# Qwiic_1Wire_to_I2C_Bridge_DS28E17_MILLAB.net
KiCad netlist of a schematic drawn in EAGLE
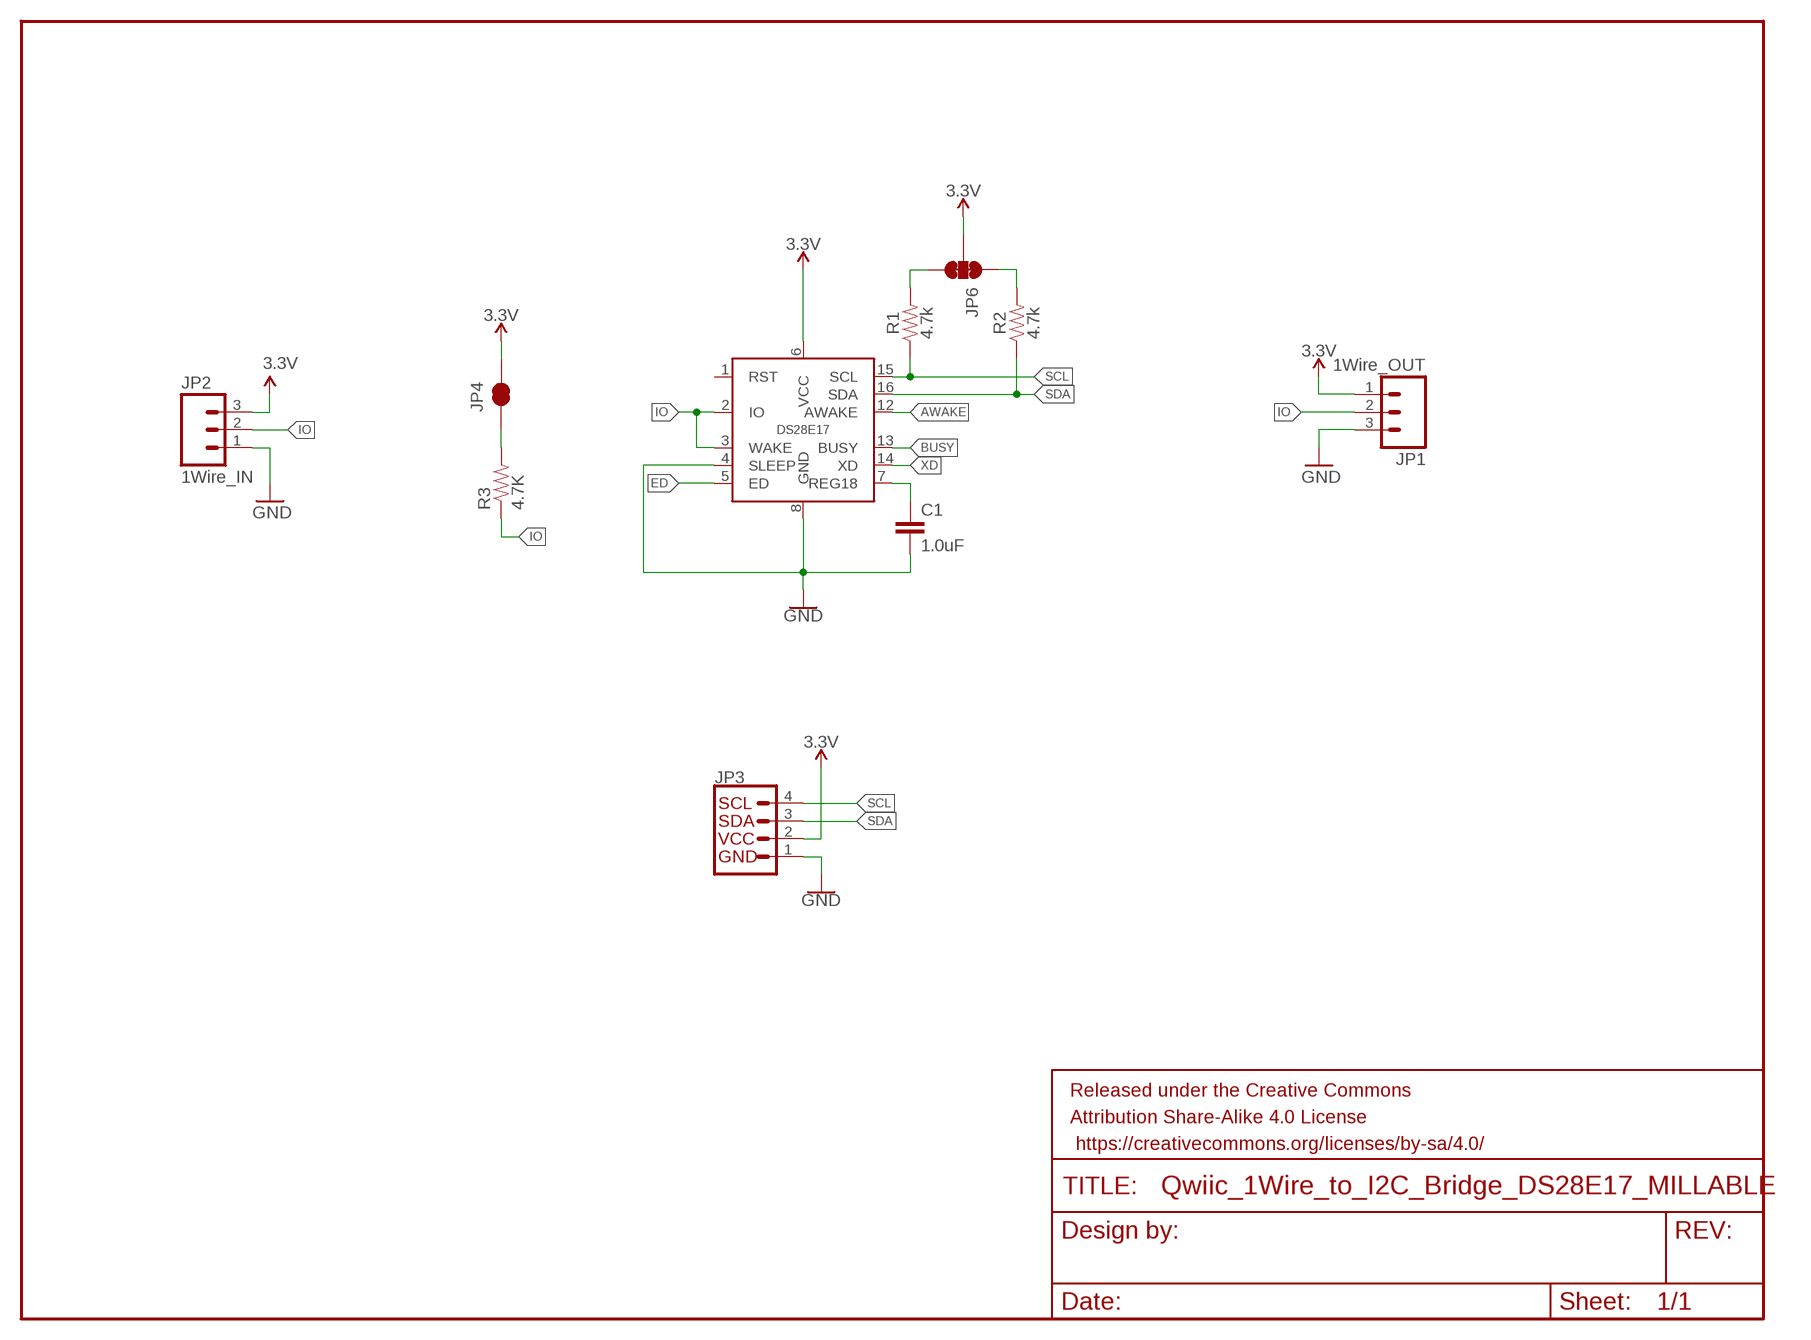
[diagram p0: schematic, sheet 1]

(export (version "E")
  (design (tool "Eeschema 10.0.6"))
  (components
    (comp (ref "C1")
      (value "1.0uF")
      (footprint "eagle-import:0603")
      (libsource (lib "eagle-import") (part "1.0UF-0603-16V-10%"))
    )
    (comp (ref "FRAME1")
      (value "FRAME-LETTER")
      (footprint "eagle-import:CREATIVE_COMMONS")
      (libsource (lib "eagle-import") (part "FRAME-LETTER"))
    )
    (comp (ref "JP1")
      (value "1Wire_OUT")
      (footprint "eagle-import:1X03")
      (libsource (lib "eagle-import") (part "M03PTH"))
    )
    (comp (ref "JP2")
      (value "1Wire_IN")
      (footprint "eagle-import:1X03")
      (libsource (lib "eagle-import") (part "M03PTH"))
    )
    (comp (ref "JP3")
      (value "I2C_STANDARDJS-1MM")
      (footprint "eagle-import:1X04_1MM_RA")
      (libsource (lib "eagle-import") (part "I2C_STANDARDJS-1MM"))
    )
    (comp (ref "JP4")
      (value "JUMPER-SMT_2_NC_TRACE_NO-SILK")
      (footprint "eagle-import:SMT-JUMPER_2_NC_TRACE_NO-SILK")
      (libsource (lib "eagle-import") (part "JUMPER-SMT_2_NC_TRACE_NO-SILK"))
    )
    (comp (ref "JP6")
      (value "JUMPER-SMT_3_2-NC_TRACE_NO-SILK")
      (footprint "eagle-import:SMT-JUMPER_3_2-NC_TRACE_NO-SILK")
      (libsource (lib "eagle-import") (part "JUMPER-SMT_3_2-NC_TRACE_NO-SILK"))
    )
    (comp (ref "R1")
      (value "4.7k")
      (footprint "eagle-import:0603")
      (libsource (lib "eagle-import") (part "4.7KOHM-0603-1/10W-1%"))
    )
    (comp (ref "R2")
      (value "4.7k")
      (footprint "eagle-import:0603")
      (libsource (lib "eagle-import") (part "4.7KOHM-0603-1/10W-1%"))
    )
    (comp (ref "R3")
      (value "4.7K")
      (footprint "eagle-import:0603-RES")
      (libsource (lib "eagle-import") (part "4.7KOHM-1/10W-1%(0603)"))
    )
    (comp (ref "U$2")
      (value "DS28E17")
      (footprint "eagle-import:TQFN-16_4X4")
      (libsource (lib "eagle-import") (part "DS28E17"))
    )
  )
  (nets
    (net (code "1") (name "3.3V") (class "Default")
      (node (ref "JP1") (pin "1") (pinfunction "1_1") (pintype "passive"))
      (node (ref "JP2") (pin "3") (pinfunction "3_3") (pintype "passive"))
      (node (ref "JP3") (pin "2") (pinfunction "VCC_2") (pintype "power_in"))
      (node (ref "JP4") (pin "2") (pinfunction "2_2") (pintype "passive"))
      (node (ref "JP6") (pin "2") (pinfunction "2_2") (pintype "passive"))
      (node (ref "U$2") (pin "6") (pinfunction "VCC_6") (pintype "power_in"))
    )
    (net (code "2") (name "AWAKE") (class "Default")
      (node (ref "U$2") (pin "12") (pinfunction "AWAKE_12") (pintype "bidirectional"))
    )
    (net (code "3") (name "BUSY") (class "Default")
      (node (ref "U$2") (pin "13") (pinfunction "BUSY_13") (pintype "bidirectional"))
    )
    (net (code "4") (name "ED") (class "Default")
      (node (ref "U$2") (pin "5") (pinfunction "ED_5") (pintype "bidirectional"))
    )
    (net (code "5") (name "GND") (class "Default")
      (node (ref "C1") (pin "2") (pinfunction "2_2") (pintype "passive"))
      (node (ref "JP1") (pin "3") (pinfunction "3_3") (pintype "passive"))
      (node (ref "JP2") (pin "1") (pinfunction "1_1") (pintype "passive"))
      (node (ref "JP3") (pin "1") (pinfunction "GND_1") (pintype "power_in"))
      (node (ref "U$2") (pin "4") (pinfunction "SLEEP_4") (pintype "bidirectional"))
      (node (ref "U$2") (pin "8") (pinfunction "GND_8") (pintype "power_in"))
    )
    (net (code "6") (name "IO") (class "Default")
      (node (ref "JP1") (pin "2") (pinfunction "2_2") (pintype "passive"))
      (node (ref "JP2") (pin "2") (pinfunction "2_2") (pintype "passive"))
      (node (ref "R3") (pin "1") (pinfunction "1_1") (pintype "passive"))
      (node (ref "U$2") (pin "2") (pinfunction "IO_2") (pintype "bidirectional"))
      (node (ref "U$2") (pin "3") (pinfunction "WAKE_3") (pintype "bidirectional"))
    )
    (net (code "7") (name "Net-(JP4-Pad1)") (class "Default")
      (node (ref "JP4") (pin "1") (pinfunction "1_1") (pintype "passive"))
      (node (ref "R3") (pin "2") (pinfunction "2_2") (pintype "passive"))
    )
    (net (code "8") (name "Net-(JP6-Pad1)") (class "Default")
      (node (ref "JP6") (pin "1") (pinfunction "1_1") (pintype "passive"))
      (node (ref "R2") (pin "2") (pinfunction "2_2") (pintype "passive"))
    )
    (net (code "9") (name "Net-(JP6-Pad3)") (class "Default")
      (node (ref "JP6") (pin "3") (pinfunction "3_3") (pintype "passive"))
      (node (ref "R1") (pin "2") (pinfunction "2_2") (pintype "passive"))
    )
    (net (code "10") (name "Net-(U$2-REG18)") (class "Default")
      (node (ref "C1") (pin "1") (pinfunction "1_1") (pintype "passive"))
      (node (ref "U$2") (pin "7") (pinfunction "REG18_7") (pintype "bidirectional"))
    )
    (net (code "11") (name "SCL") (class "Default")
      (node (ref "JP3") (pin "4") (pinfunction "SCL_4") (pintype "passive"))
      (node (ref "R1") (pin "1") (pinfunction "1_1") (pintype "passive"))
      (node (ref "U$2") (pin "15") (pinfunction "SCL_15") (pintype "bidirectional"))
    )
    (net (code "12") (name "SDA") (class "Default")
      (node (ref "JP3") (pin "3") (pinfunction "SDA_3") (pintype "passive"))
      (node (ref "R2") (pin "1") (pinfunction "1_1") (pintype "passive"))
      (node (ref "U$2") (pin "16") (pinfunction "SDA_16") (pintype "bidirectional"))
    )
    (net (code "13") (name "XD") (class "Default")
      (node (ref "U$2") (pin "14") (pinfunction "XD_14") (pintype "bidirectional"))
    )
    (net (code "14") (name "unconnected-(U$2-RST-Pad1)") (class "Default")
      (node (ref "U$2") (pin "1") (pinfunction "RST_1") (pintype "bidirectional"))
    )
  )
)
